# 24V.net
KiCad netlist of a schematic drawn in Altium Designer
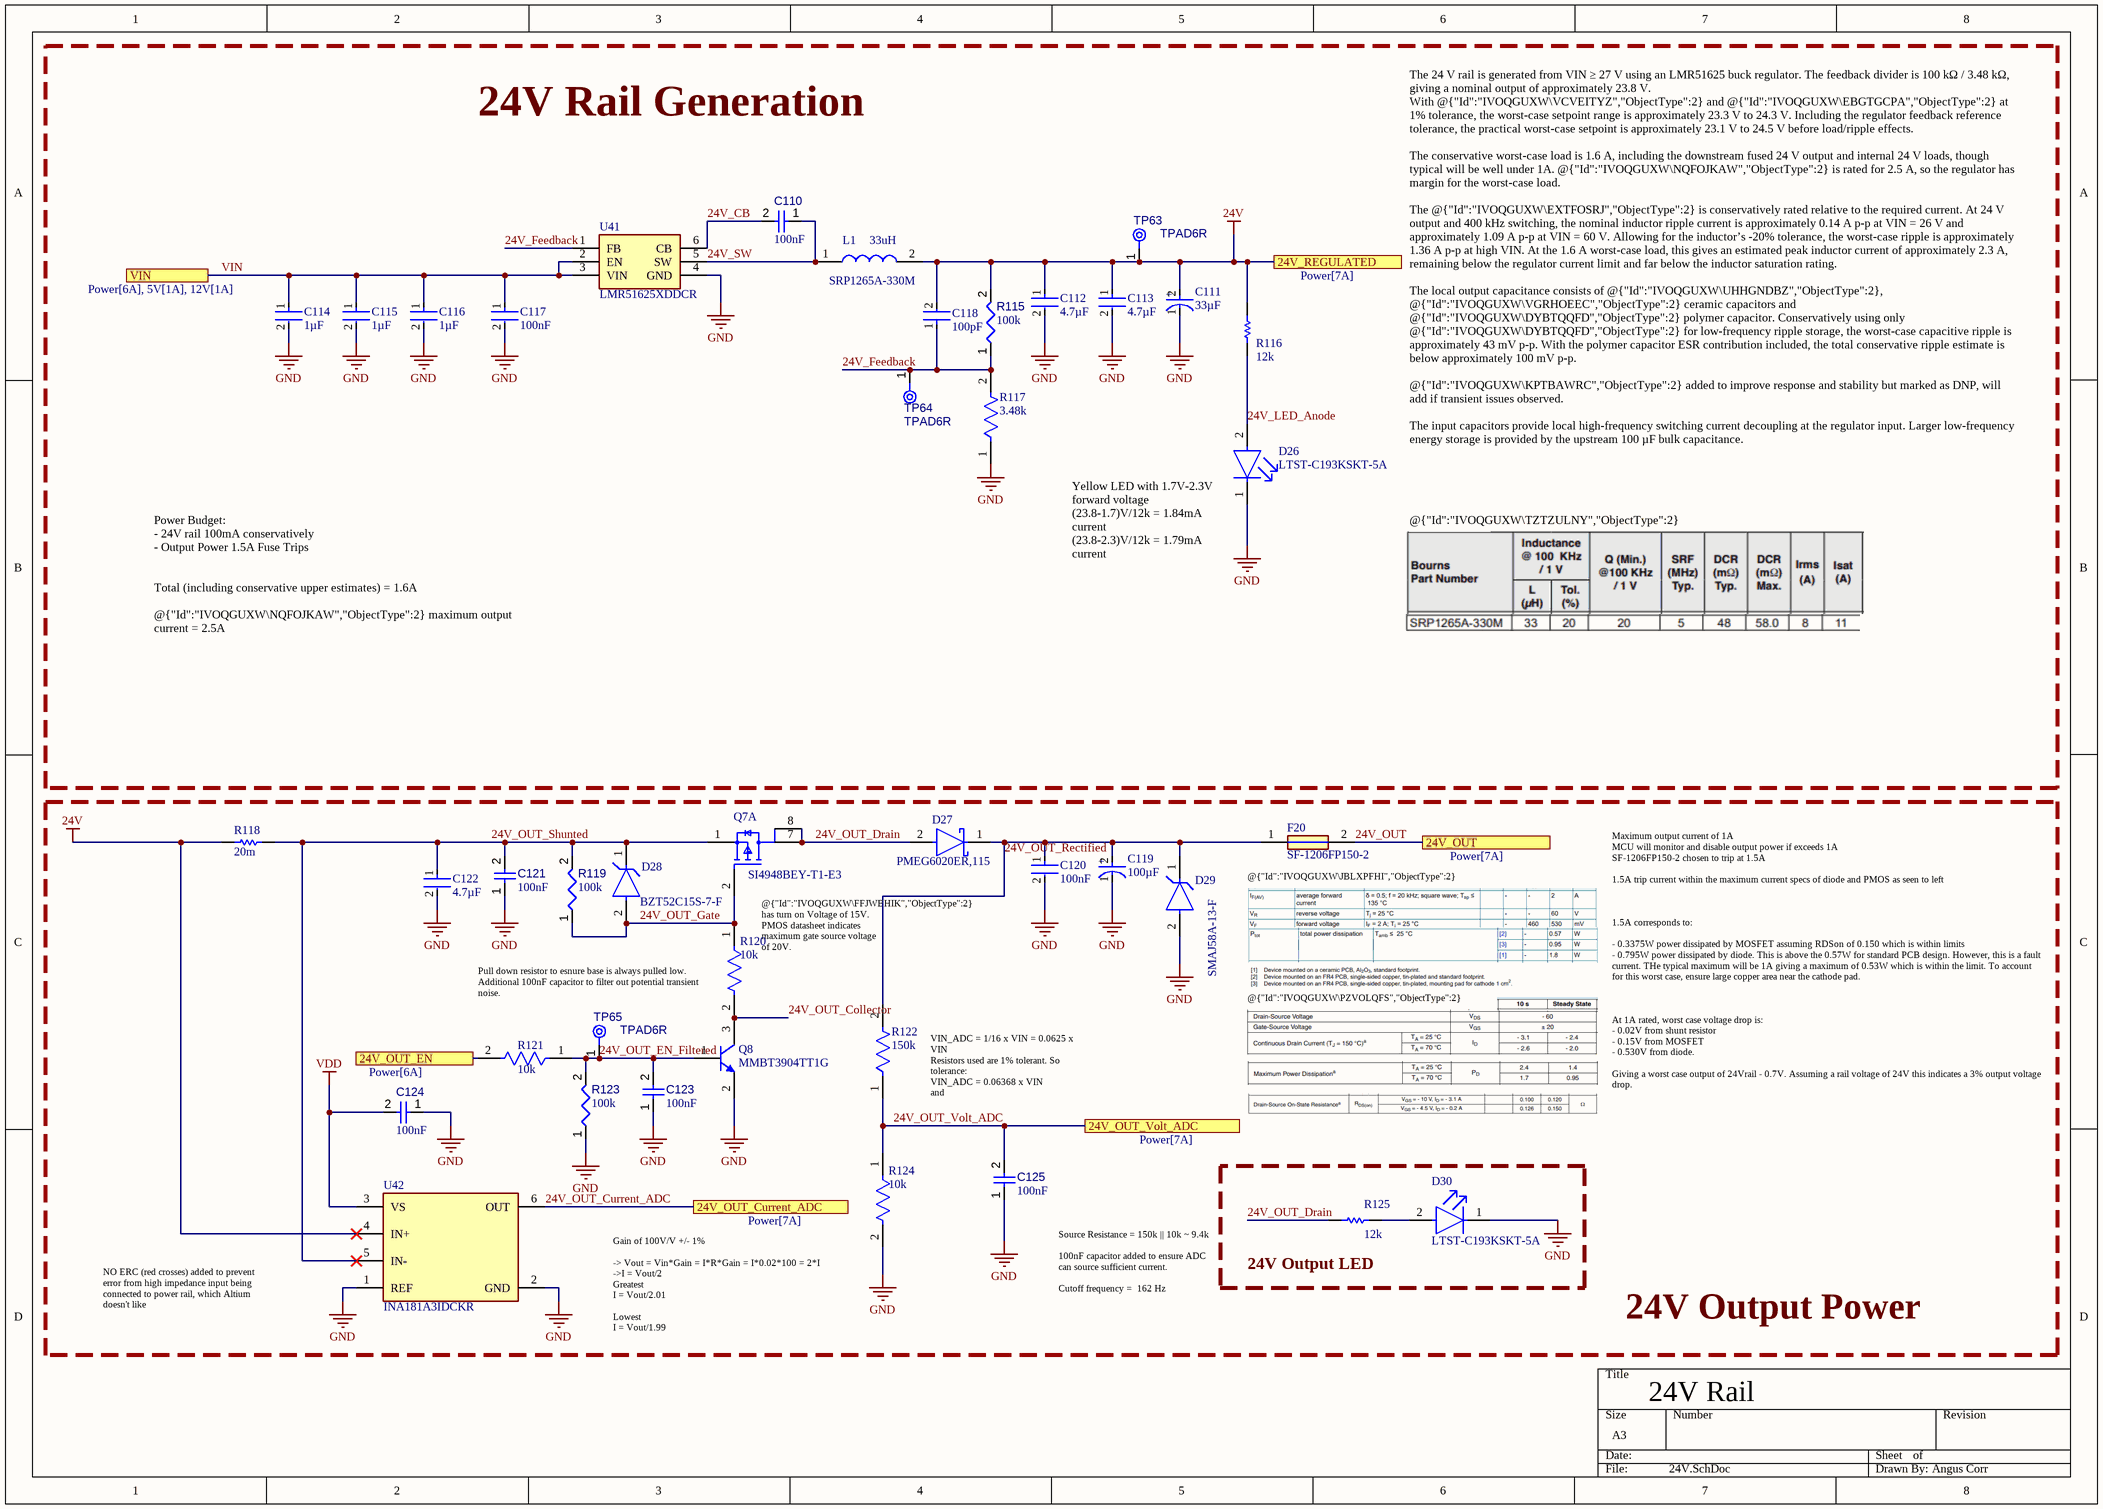
[diagram p0:  24V.SchDoc]

(export (version "E")
  (design (tool "Eeschema 10.0.6"))
  (components
    (comp (ref "C110")
      (value "100nF")
      (footprint "CAPC1608X90X40NL10T20")
      (description "Chip Capacitor, 100 nF, +/- 10%, 50 V, 0603 (1608 Metric)")
      (fields (field (name "TOLERANCE") "10%") (field (name "Comment") "Capacitor 100 nF +/-10% 50 V 0603"))
      (libsource (lib "HIL RIG FYP") (part "CAP-NP-2"))
    )
    (comp (ref "C111")
      (value "33µF")
      (footprint "FP-EEH-D8-MFG")
      (description "Cap Aluminum 33uF 50V 20% (6.3 X 7.7mm) SMD 0.04 Ohm 1600mA 5000 hr 105°C Embossed T/R")
      (fields (field (name "TOLERANCE") "20%") (field (name "Comment") "EEHZA1H330XP"))
      (libsource (lib "HIL RIG FYP") (part "a00bbbee19879c290e62620ae7e47b1"))
    )
    (comp (ref "C112")
      (value "4.7µF")
      (footprint "FP-GRM21B-0_2-e0_2_0_7-MFG")
      (description "50V 4.7uF X7R ±10% 0805 Multilayer Ceramic Capacitors MLCC - SMD/SMT ROHS")
      (fields (field (name "TOLERANCE") "10%") (field (name "Comment") "GRM21BZ71H475KE15L"))
      (libsource (lib "HIL RIG FYP") (part "b4654b650e69147ec39a6b967a45e02"))
    )
    (comp (ref "C113")
      (value "4.7µF")
      (footprint "FP-GRM21B-0_2-e0_2_0_7-MFG")
      (description "50V 4.7uF X7R ±10% 0805 Multilayer Ceramic Capacitors MLCC - SMD/SMT ROHS")
      (fields (field (name "TOLERANCE") "10%") (field (name "Comment") "GRM21BZ71H475KE15L"))
      (libsource (lib "HIL RIG FYP") (part "b4654b650e69147ec39a6b967a45e02"))
    )
    (comp (ref "C114")
      (value "1µF")
      (footprint "FP-GRJ21B-0_35-MFG")
      (description "100V 1uF X7S ±10% 0805 Multilayer Ceramic Capacitors MLCC - SMD/SMT ROHS")
      (fields (field (name "TOLERANCE") "10%") (field (name "Comment") "GRJ21BC72A105KE11L"))
      (libsource (lib "HIL RIG FYP") (part "b4654b650e69147ec39a6b967a45e02"))
    )
    (comp (ref "C115")
      (value "1µF")
      (footprint "FP-GRJ21B-0_35-MFG")
      (description "100V 1uF X7S ±10% 0805 Multilayer Ceramic Capacitors MLCC - SMD/SMT ROHS")
      (fields (field (name "TOLERANCE") "10%") (field (name "Comment") "GRJ21BC72A105KE11L"))
      (libsource (lib "HIL RIG FYP") (part "b4654b650e69147ec39a6b967a45e02"))
    )
    (comp (ref "C116")
      (value "1µF")
      (footprint "FP-GRJ21B-0_35-MFG")
      (description "100V 1uF X7S ±10% 0805 Multilayer Ceramic Capacitors MLCC - SMD/SMT ROHS")
      (fields (field (name "TOLERANCE") "10%") (field (name "Comment") "GRJ21BC72A105KE11L"))
      (libsource (lib "HIL RIG FYP") (part "b4654b650e69147ec39a6b967a45e02"))
    )
    (comp (ref "C117")
      (value "100nF")
      (footprint "FP-GRM31C-0_2-e0_3_0_8-IPC_C")
      (description "100V 100nF C0G ±5% 1206 Multilayer Ceramic Capacitors MLCC - SMD/SMT ROHS")
      (fields (field (name "TOLERANCE") "5%") (field (name "Comment") "GRM31C5C2A104JA01L"))
      (libsource (lib "HIL RIG FYP") (part "02cd4be3c70576c341d710602a673aa"))
    )
    (comp (ref "C118")
      (value "100pF")
      (footprint "FP-C0603C-CF-IPC_B")
      (description "50V 100pF C0G ±1% 0603 Multilayer Ceramic Capacitors MLCC - SMD/SMT ROHS")
      (fields (field (name "TOLERANCE") "1%") (field (name "Comment") "C0603C101F5GACTU"))
      (libsource (lib "HIL RIG FYP") (part "b4654b650e69147ec39a6b967a45e02"))
    )
    (comp (ref "C119")
      (value "100µF")
      (footprint "FP-MVYAKE0-MFG")
      (description "Cap Aluminum 100uF 100V 20% (12.5 X 13.5mm) SMD 450mA 5000h 105°C T/R")
      (fields (field (name "TOLERANCE") "20%") (field (name "Comment") "EMVY101ARA101MKE0S"))
      (libsource (lib "HIL RIG FYP") (part "203bc49f2ac43e59fd269a8c329ed05"))
    )
    (comp (ref "C120")
      (value "100nF")
      (footprint "FP-GRM31C-0_2-e0_3_0_8-IPC_C")
      (description "100V 100nF C0G ±5% 1206 Multilayer Ceramic Capacitors MLCC - SMD/SMT ROHS")
      (fields (field (name "TOLERANCE") "5%") (field (name "Comment") "GRM31C5C2A104JA01L"))
      (libsource (lib "HIL RIG FYP") (part "02cd4be3c70576c341d710602a673aa"))
    )
    (comp (ref "C121")
      (value "100nF")
      (footprint "CAPC1608X90X40NL10T20")
      (description "Chip Capacitor, 100 nF, +/- 10%, 50 V, 0603 (1608 Metric)")
      (fields (field (name "TOLERANCE") "10%") (field (name "Comment") "Capacitor 100 nF +/-10% 50 V 0603"))
      (libsource (lib "HIL RIG FYP") (part "CAP-NP-2"))
    )
    (comp (ref "C122")
      (value "4.7µF")
      (footprint "FP-GRM21B-0_2-e0_2_0_7-MFG")
      (description "50V 4.7uF X7R ±10% 0805 Multilayer Ceramic Capacitors MLCC - SMD/SMT ROHS")
      (fields (field (name "TOLERANCE") "10%") (field (name "Comment") "GRM21BZ71H475KE15L"))
      (libsource (lib "HIL RIG FYP") (part "b4654b650e69147ec39a6b967a45e02"))
    )
    (comp (ref "C123")
      (value "100nF")
      (footprint "CAPC1608X90X40NL10T20")
      (description "Chip Capacitor, 100 nF, +/- 10%, 50 V, 0603 (1608 Metric)")
      (fields (field (name "TOLERANCE") "10%") (field (name "Comment") "Capacitor 100 nF +/-10% 50 V 0603"))
      (libsource (lib "HIL RIG FYP") (part "CAP-NP-2"))
    )
    (comp (ref "C124")
      (value "100nF")
      (footprint "CAPC1608X90X40NL10T20")
      (description "Chip Capacitor, 100 nF, +/- 10%, 50 V, 0603 (1608 Metric)")
      (fields (field (name "TOLERANCE") "10%") (field (name "Comment") "Capacitor 100 nF +/-10% 50 V 0603"))
      (libsource (lib "HIL RIG FYP") (part "CAP-NP-2"))
    )
    (comp (ref "C125")
      (value "100nF")
      (footprint "CAPC1608X90X40NL10T20")
      (description "Chip Capacitor, 100 nF, +/- 10%, 50 V, 0603 (1608 Metric)")
      (fields (field (name "TOLERANCE") "10%") (field (name "Comment") "Capacitor 100 nF +/-10% 50 V 0603"))
      (libsource (lib "HIL RIG FYP") (part "CAP-NP-2"))
    )
    (comp (ref "D26")
      (value "LTST-C193KSKT-5A")
      (footprint "FP-LTST-C193KGKT-5A-MFG")
      (description "LED yellow 0603 wavelength 587~594.5nm light intensity 7.1~45mcd Front Mounting")
      (libsource (lib "HIL RIG FYP") (part "8706943c75ba83719d021d2fdc84c58"))
    )
    (comp (ref "D27")
      (value "PMEG6020ER,115")
      (footprint "FP-SOD123W-MFG")
      (description "PMEG6020 Series 60 V 2 A SMT Llow VF MEGA Schottky Barrier Rectifier - SOD-123W")
      (libsource (lib "HIL RIG FYP") (part "1d6ec82d83fb6aee721767c19dac4b9"))
    )
    (comp (ref "D28")
      (value "BZT52C15S-7-F")
      (footprint "FP-SOD323-IPC_A")
      (description "BZT52C15S Series 200 mW 15 V 10 mA Surface Mount Zener Diode - SOD-323")
      (libsource (lib "HIL RIG FYP") (part "f813f71cba58e380607f5dd3caf9714"))
    )
    (comp (ref "D29")
      (value "SMAJ58A-13-F")
      (footprint "FP-SMA-MFG")
      (description "SMAJ Series 58 V 400 W SMT Uni-Directional TVS Diode - DO-214AC")
      (libsource (lib "HIL RIG FYP") (part "f813f71cba58e380607f5dd3caf9714"))
    )
    (comp (ref "D30")
      (value "LTST-C193KSKT-5A")
      (footprint "FP-LTST-C193KGKT-5A-MFG")
      (description "LED yellow 0603 wavelength 587~594.5nm light intensity 7.1~45mcd Front Mounting")
      (libsource (lib "HIL RIG FYP") (part "8706943c75ba83719d021d2fdc84c58"))
    )
    (comp (ref "F20")
      (value "SF-1206FP150-2")
      (footprint "FUSC3116X70N")
      (description "Surface Mount Fuses 1.5A Fast Acting 1206 Singlfuse")
      (fields (field (name "MOUSER PART NUMBER") "652-SF-1206FP150-2"))
      (libsource (lib "HIL RIG FYP") (part "SF-1206FP150-2"))
    )
    (comp (ref "L1")
      (value "SRP1265A-330M")
      (footprint "SRP1265A")
      (description "Bourns SRP1265A Series Shielded Wire-wound SMD Inductor with a Carbonyl Powder Core")
      (fields (field (name "MOUSER PART NUMBER") "652-SRP1265A-330M"))
      (libsource (lib "HIL RIG FYP") (part "VLS4015CX-4R7M-H"))
    )
    (comp (ref "Q7")
      (value "SI4948BEY-T1-E3")
      (footprint "FP-C-06527-IPC_B")
      (description "Dual P-Channel 60 V 0.12 Ohms Surface Mount Power Mosfet - SOIC-8")
      (libsource (lib "HIL RIG FYP") (part "8dc75c867fb8938c255332086adbf49"))
    )
    (comp (ref "Q8")
      (value "MMBT3904TT1G")
      (footprint "ONSC-SC-75-3-463-01_V")
      (description "on Semi MMBT3904TT1G NPN Bipolar Transistor, 0.2 A, 40 V, 3-PIN SOT-416")
      (libsource (lib "HIL RIG FYP") (part "ONSC-NPN-B1E2C3-3"))
    )
    (comp (ref "R115")
      (value "100k")
      (footprint "FP-AC0603-IPC_C")
      (description "Res Thick Film 0603 100K Ohm 1% 0.1W(1/10W) ±100ppm/C Pad SMD T/R Automotive")
      (fields (field (name "TOLERANCE") "1%") (field (name "Comment") "AC0603FR-07100KL"))
      (libsource (lib "HIL RIG FYP") (part "RES-2"))
    )
    (comp (ref "R116")
      (value "12k")
      (footprint "RESC1608X55X25LL10T15")
      (description "100mW Thick Film Resistors 75V ±100ppm/℃ ±1% 12kΩ 0603 Chip Resistor - Surface Mount ROHS")
      (fields (field (name "TOLERANCE") "1%") (field (name "Comment") "RC0603FR-0712KL"))
      (libsource (lib "") (part "RES-2_1"))
    )
    (comp (ref "R117")
      (value "3.48k")
      (footprint "FP-AC0603-IPC_C")
      (description "Res Thick Film 0603 3.48K Ohm 1% 0.1W(1/10W) ±100ppm/C Pad SMD T/R Automotive AEC-Q200")
      (fields (field (name "TOLERANCE") "1%") (field (name "Comment") "AC0603FR-073K48L"))
      (libsource (lib "HIL RIG FYP") (part "1029c3af85768c4190bb7ad29bc67b5"))
    )
    (comp (ref "R118")
      (value "20m")
      (footprint "RESC3216X89X51NL25T25")
      (description "Res Metal Strip 1206 0.02 Ohm 1% 1/4W ±75ppm/°C Molded SMD SMD Embossed Plastic T/R")
      (fields (field (name "TOLERANCE") "1%") (field (name "Comment") "WSL1206R0200FEA"))
      (libsource (lib "HIL RIG FYP") (part "RES"))
    )
    (comp (ref "R119")
      (value "100k")
      (footprint "FP-AC0603-IPC_C")
      (description "Res Thick Film 0603 100K Ohm 1% 0.1W(1/10W) ±100ppm/C Pad SMD T/R Automotive")
      (fields (field (name "TOLERANCE") "1%") (field (name "Comment") "AC0603FR-07100KL"))
      (libsource (lib "HIL RIG FYP") (part "RES-2"))
    )
    (comp (ref "R120")
      (value "10k")
      (footprint "FP-RT0603-IPC_C")
      (description "Res Thin Film 0603 10K Ohm 0.1% 1/10W ¦25ppm/¦C SMD Paper T/R")
      (fields (field (name "TOLERANCE") "0.1%") (field (name "Comment") "RT0603BRD0710KL"))
      (libsource (lib "HIL RIG FYP") (part "1029c3af85768c4190bb7ad29bc67b5"))
    )
    (comp (ref "R121")
      (value "10k")
      (footprint "FP-RT0603-IPC_C")
      (description "Res Thin Film 0603 10K Ohm 0.1% 1/10W ¦25ppm/¦C SMD Paper T/R")
      (fields (field (name "TOLERANCE") "0.1%") (field (name "Comment") "RT0603BRD0710KL"))
      (libsource (lib "HIL RIG FYP") (part "1029c3af85768c4190bb7ad29bc67b5"))
    )
    (comp (ref "R122")
      (value "150k")
      (footprint "FP-CRGCQ0603-IPC_A")
      (description "Res Thick Film 0603 150K Ohm 1% 0.1W(1/10W) ±100ppm/C Pad SMD Automotive T/R")
      (fields (field (name "TOLERANCE") "1%") (field (name "Comment") "CRGCQ0603F150K"))
      (libsource (lib "HIL RIG FYP") (part "1029c3af85768c4190bb7ad29bc67b5"))
    )
    (comp (ref "R123")
      (value "100k")
      (footprint "FP-AC0603-IPC_C")
      (description "Res Thick Film 0603 100K Ohm 1% 0.1W(1/10W) ±100ppm/C Pad SMD T/R Automotive")
      (fields (field (name "TOLERANCE") "1%") (field (name "Comment") "AC0603FR-07100KL"))
      (libsource (lib "HIL RIG FYP") (part "RES-2"))
    )
    (comp (ref "R124")
      (value "10k")
      (footprint "FP-RT0603-IPC_C")
      (description "Res Thin Film 0603 10K Ohm 0.1% 1/10W ¦25ppm/¦C SMD Paper T/R")
      (fields (field (name "TOLERANCE") "0.1%") (field (name "Comment") "RT0603BRD0710KL"))
      (libsource (lib "HIL RIG FYP") (part "1029c3af85768c4190bb7ad29bc67b5"))
    )
    (comp (ref "R125")
      (value "12k")
      (footprint "RESC1608X55X25LL10T15")
      (description "100mW Thick Film Resistors 75V ±100ppm/℃ ±1% 12kΩ 0603 Chip Resistor - Surface Mount ROHS")
      (fields (field (name "TOLERANCE") "1%") (field (name "Comment") "RC0603FR-0712KL"))
      (libsource (lib "") (part "RES-2_1"))
    )
    (comp (ref "TP63")
      (value "TPAD6R")
      (footprint "TP06R")
      (description "0.6mm round")
      (libsource (lib "HIL RIG FYP") (part "CMP-001-0001-4"))
    )
    (comp (ref "TP64")
      (value "TPAD6R")
      (footprint "TP06R")
      (description "0.6mm round")
      (libsource (lib "HIL RIG FYP") (part "CMP-001-0001-4"))
    )
    (comp (ref "TP65")
      (value "TPAD6R")
      (footprint "TP06R")
      (description "0.6mm round")
      (libsource (lib "HIL RIG FYP") (part "CMP-001-0001-4"))
    )
    (comp (ref "U41")
      (value "LMR51625XDDCR")
      (footprint "SOT95P280X110-6N")
      (description "Switching Voltage Regulators SIMPLE SWITCHER synchronous buck converter with 4.3V-to-60V")
      (fields (field (name "MOUSER PART NUMBER") "595-LMR51625XDDCR"))
      (libsource (lib "HIL RIG FYP") (part "LMR51625XDDCR"))
    )
    (comp (ref "U42")
      (value "INA181A3IDCKR")
      (footprint "FP-DCK0006A-IPC_A")
      (description "26-V bi-directional 350-kHz current-sense amplifier 6-SC70 -40 to 125")
      (libsource (lib "HIL RIG FYP") (part "a7b5cee9b6bc60f4871af0ee2c3b109"))
    )
  )
  (nets
    (net (code "1") (name "/24V_CB") (class "Default")
      (node (ref "C110") (pin "2") (pinfunction "2_2") (pintype "passive"))
      (node (ref "U41") (pin "6") (pinfunction "CB_6") (pintype "passive"))
    )
    (net (code "2") (name "/24V_Feedback") (class "Default")
      (node (ref "C118") (pin "1") (pinfunction "1_1") (pintype "passive"))
      (node (ref "R115") (pin "1") (pinfunction "1_1") (pintype "passive"))
      (node (ref "R117") (pin "2") (pinfunction "2_2") (pintype "passive"))
      (node (ref "TP64") (pin "1") (pinfunction "TP_1") (pintype "passive"))
      (node (ref "U41") (pin "1") (pinfunction "FB_1") (pintype "passive"))
    )
    (net (code "3") (name "/24V_LED_Anode") (class "Default")
      (node (ref "D26") (pin "2") (pinfunction "A_2") (pintype "passive"))
      (node (ref "R116") (pin "2") (pinfunction "2_2") (pintype "passive"))
    )
    (net (code "4") (name "/24V_OUT") (class "Default")
      (node (ref "F20") (pin "2") (pinfunction "2_2") (pintype "passive"))
    )
    (net (code "5") (name "/24V_OUT_Collector") (class "Default")
      (node (ref "Q8") (pin "3") (pinfunction "C_3") (pintype "passive"))
      (node (ref "R120") (pin "2") (pinfunction "2_2") (pintype "passive"))
    )
    (net (code "6") (name "/24V_OUT_Current_ADC") (class "Default")
      (node (ref "U42") (pin "6") (pinfunction "OUT_6") (pintype "passive"))
    )
    (net (code "7") (name "/24V_OUT_Drain") (class "Default")
      (node (ref "D27") (pin "2") (pinfunction "A_2") (pintype "passive"))
      (node (ref "Q7") (pin "7") (pinfunction "D1_7") (pintype "passive"))
      (node (ref "Q7") (pin "8") (pinfunction "D1_8") (pintype "passive"))
      (node (ref "R125") (pin "1") (pinfunction "1_1") (pintype "passive"))
    )
    (net (code "8") (name "/24V_OUT_EN") (class "Default")
      (node (ref "R121") (pin "2") (pinfunction "2_2") (pintype "passive"))
    )
    (net (code "9") (name "/24V_OUT_EN_Filtered") (class "Default")
      (node (ref "C123") (pin "2") (pinfunction "2_2") (pintype "passive"))
      (node (ref "Q8") (pin "1") (pinfunction "B_1") (pintype "passive"))
      (node (ref "R121") (pin "1") (pinfunction "1_1") (pintype "passive"))
      (node (ref "R123") (pin "2") (pinfunction "2_2") (pintype "passive"))
      (node (ref "TP65") (pin "1") (pinfunction "TP_1") (pintype "passive"))
    )
    (net (code "10") (name "/24V_OUT_Gate") (class "Default")
      (node (ref "D28") (pin "2") (pinfunction "A_2") (pintype "passive"))
      (node (ref "Q7") (pin "2") (pinfunction "G1_2") (pintype "passive"))
      (node (ref "R119") (pin "1") (pinfunction "1_1") (pintype "passive"))
      (node (ref "R120") (pin "1") (pinfunction "1_1") (pintype "passive"))
    )
    (net (code "11") (name "/24V_OUT_Rectified") (class "Default")
      (node (ref "C119") (pin "2") (pinfunction "A_2") (pintype "passive"))
      (node (ref "C120") (pin "1") (pinfunction "1_1") (pintype "passive"))
      (node (ref "D27") (pin "1") (pinfunction "C_1") (pintype "passive"))
      (node (ref "D29") (pin "1") (pinfunction "C_1") (pintype "passive"))
      (node (ref "F20") (pin "1") (pinfunction "1_1") (pintype "passive"))
      (node (ref "R122") (pin "2") (pinfunction "2_2") (pintype "passive"))
    )
    (net (code "12") (name "/24V_OUT_Shunted") (class "Default")
      (node (ref "C121") (pin "2") (pinfunction "2_2") (pintype "passive"))
      (node (ref "C122") (pin "1") (pinfunction "1_1") (pintype "passive"))
      (node (ref "D28") (pin "1") (pinfunction "C_1") (pintype "passive"))
      (node (ref "Q7") (pin "1") (pinfunction "S1_1") (pintype "passive"))
      (node (ref "R118") (pin "2") (pinfunction "2_2") (pintype "passive"))
      (node (ref "R119") (pin "2") (pinfunction "2_2") (pintype "passive"))
      (node (ref "U42") (pin "5") (pinfunction "IN-_5") (pintype "tri_state"))
    )
    (net (code "13") (name "/24V_OUT_Volt_ADC") (class "Default")
      (node (ref "C125") (pin "2") (pinfunction "2_2") (pintype "passive"))
      (node (ref "R122") (pin "1") (pinfunction "1_1") (pintype "passive"))
      (node (ref "R124") (pin "1") (pinfunction "1_1") (pintype "passive"))
    )
    (net (code "14") (name "/24V_SW") (class "Default")
      (node (ref "C110") (pin "1") (pinfunction "1_1") (pintype "passive"))
      (node (ref "L1") (pin "1") (pinfunction "1_1") (pintype "passive"))
      (node (ref "U41") (pin "5") (pinfunction "SW_5") (pintype "passive"))
    )
    (net (code "15") (name "/VIN") (class "Default")
      (node (ref "C114") (pin "1") (pinfunction "1_1") (pintype "passive"))
      (node (ref "C115") (pin "1") (pinfunction "1_1") (pintype "passive"))
      (node (ref "C116") (pin "1") (pinfunction "1_1") (pintype "passive"))
      (node (ref "C117") (pin "1") (pinfunction "1_1") (pintype "passive"))
      (node (ref "U41") (pin "2") (pinfunction "EN_2") (pintype "passive"))
      (node (ref "U41") (pin "3") (pinfunction "VIN_3") (pintype "passive"))
    )
    (net (code "16") (name "24V") (class "Default")
      (node (ref "C111") (pin "2") (pinfunction "A_2") (pintype "passive"))
      (node (ref "C112") (pin "1") (pinfunction "1_1") (pintype "passive"))
      (node (ref "C113") (pin "1") (pinfunction "1_1") (pintype "passive"))
      (node (ref "C118") (pin "2") (pinfunction "2_2") (pintype "passive"))
      (node (ref "L1") (pin "2") (pinfunction "2_2") (pintype "passive"))
      (node (ref "R115") (pin "2") (pinfunction "2_2") (pintype "passive"))
      (node (ref "R116") (pin "1") (pinfunction "1_1") (pintype "passive"))
      (node (ref "R118") (pin "1") (pinfunction "1_1") (pintype "passive"))
      (node (ref "TP63") (pin "1") (pinfunction "TP_1") (pintype "passive"))
      (node (ref "U42") (pin "4") (pinfunction "IN+_4") (pintype "tri_state"))
    )
    (net (code "17") (name "GND") (class "Default")
      (node (ref "C111") (pin "1") (pinfunction "C_1") (pintype "passive"))
      (node (ref "C112") (pin "2") (pinfunction "2_2") (pintype "passive"))
      (node (ref "C113") (pin "2") (pinfunction "2_2") (pintype "passive"))
      (node (ref "C114") (pin "2") (pinfunction "2_2") (pintype "passive"))
      (node (ref "C115") (pin "2") (pinfunction "2_2") (pintype "passive"))
      (node (ref "C116") (pin "2") (pinfunction "2_2") (pintype "passive"))
      (node (ref "C117") (pin "2") (pinfunction "2_2") (pintype "passive"))
      (node (ref "C119") (pin "1") (pinfunction "C_1") (pintype "passive"))
      (node (ref "C120") (pin "2") (pinfunction "2_2") (pintype "passive"))
      (node (ref "C121") (pin "1") (pinfunction "1_1") (pintype "passive"))
      (node (ref "C122") (pin "2") (pinfunction "2_2") (pintype "passive"))
      (node (ref "C123") (pin "1") (pinfunction "1_1") (pintype "passive"))
      (node (ref "C124") (pin "1") (pinfunction "1_1") (pintype "passive"))
      (node (ref "C125") (pin "1") (pinfunction "1_1") (pintype "passive"))
      (node (ref "D26") (pin "1") (pinfunction "C_1") (pintype "passive"))
      (node (ref "D29") (pin "2") (pinfunction "A_2") (pintype "passive"))
      (node (ref "D30") (pin "1") (pinfunction "C_1") (pintype "passive"))
      (node (ref "Q8") (pin "2") (pinfunction "E_2") (pintype "passive"))
      (node (ref "R117") (pin "1") (pinfunction "1_1") (pintype "passive"))
      (node (ref "R123") (pin "1") (pinfunction "1_1") (pintype "passive"))
      (node (ref "R124") (pin "2") (pinfunction "2_2") (pintype "passive"))
      (node (ref "U41") (pin "4") (pinfunction "GND_4") (pintype "passive"))
      (node (ref "U42") (pin "1") (pinfunction "REF_1") (pintype "passive"))
      (node (ref "U42") (pin "2") (pinfunction "GND_2") (pintype "power_in"))
    )
    (net (code "18") (name "Net-(D30-A)") (class "Default")
      (node (ref "D30") (pin "2") (pinfunction "A_2") (pintype "passive"))
      (node (ref "R125") (pin "2") (pinfunction "2_2") (pintype "passive"))
    )
    (net (code "19") (name "VDD") (class "Default")
      (node (ref "C124") (pin "2") (pinfunction "2_2") (pintype "passive"))
      (node (ref "U42") (pin "3") (pinfunction "VS_3") (pintype "power_in"))
    )
  )
)
